# ESP32UsbHost.net
KiCad netlist of a schematic drawn in EAGLE
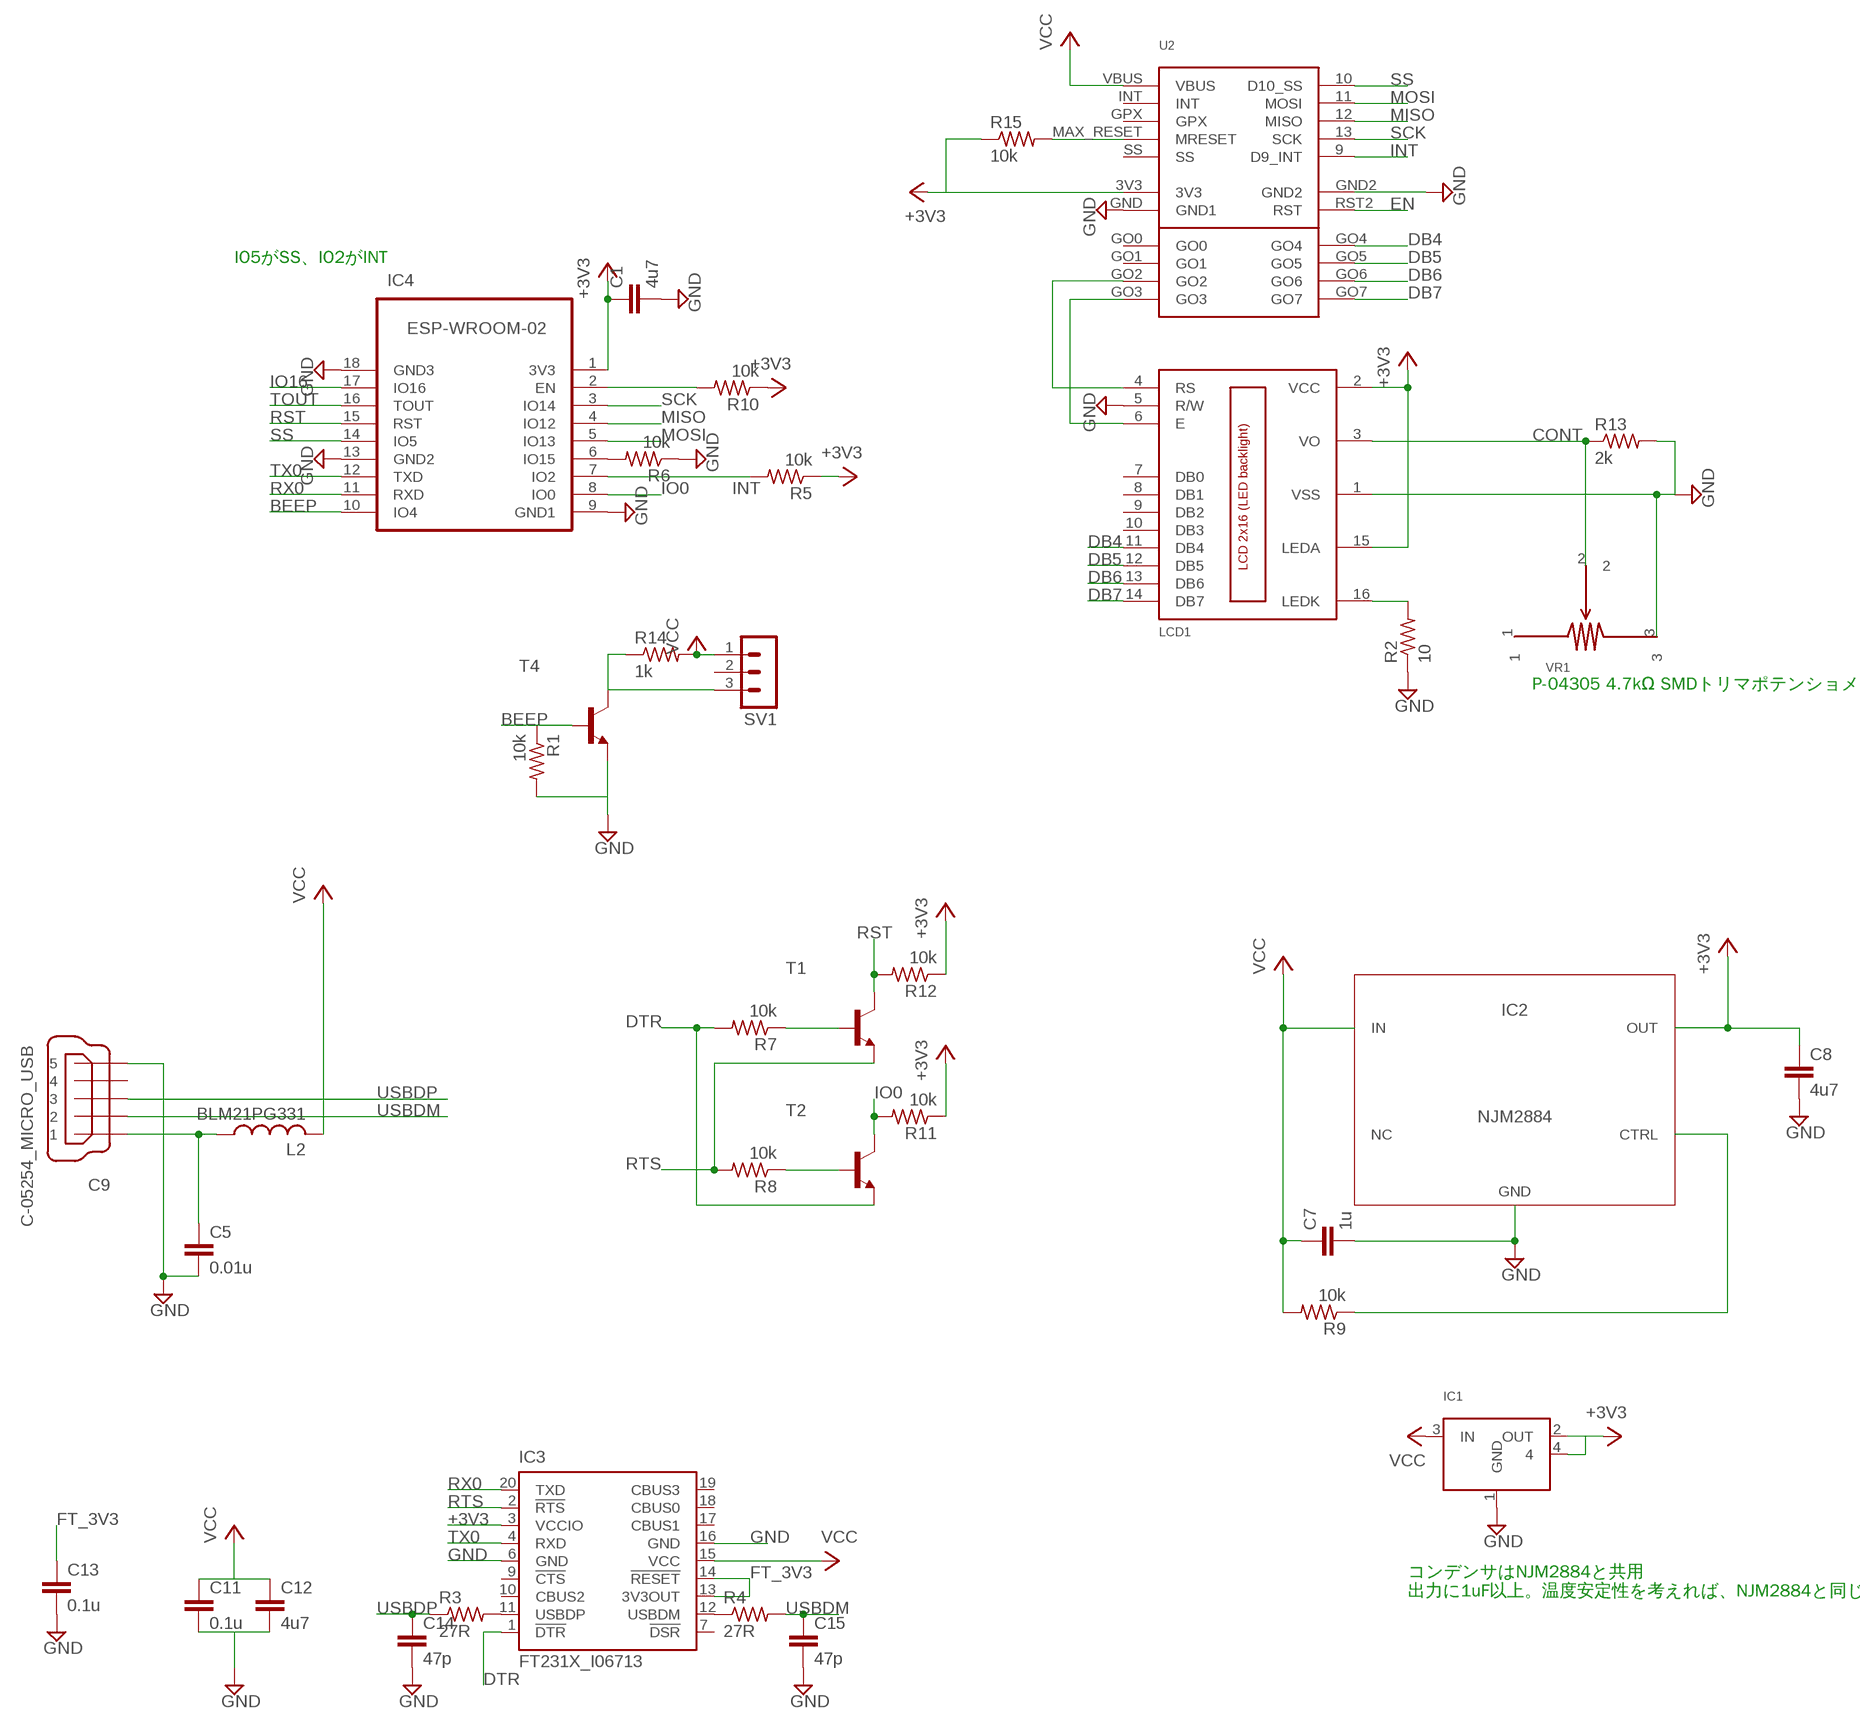
[diagram p0: schematic, sheet 1]

(export (version "E")
  (design (tool "Eeschema 10.0.6"))
  (components
    (comp (ref "C1")
      (value "4u7")
      (footprint "eagle-import:C0603")
      (libsource (lib "eagle-import") (part "C-EUC0603"))
    )
    (comp (ref "C5")
      (value "0.01u")
      (footprint "eagle-import:C0603")
      (libsource (lib "eagle-import") (part "C-EUC0603"))
    )
    (comp (ref "C7")
      (value "1u")
      (footprint "eagle-import:C0603")
      (libsource (lib "eagle-import") (part "C-EUC0603"))
    )
    (comp (ref "C8")
      (value "4u7")
      (footprint "eagle-import:C0603")
      (libsource (lib "eagle-import") (part "C-EUC0603"))
    )
    (comp (ref "C9")
      (value "C-05254_MICRO_USB")
      (footprint "eagle-import:C-05254_MICRO_USB")
      (libsource (lib "eagle-import") (part "C-05254_MICRO_USB"))
    )
    (comp (ref "C11")
      (value "0.1u")
      (footprint "eagle-import:C0603")
      (libsource (lib "eagle-import") (part "C-EUC0603"))
    )
    (comp (ref "C12")
      (value "4u7")
      (footprint "eagle-import:C0603")
      (libsource (lib "eagle-import") (part "C-EUC0603"))
    )
    (comp (ref "C13")
      (value "0.1u")
      (footprint "eagle-import:C0603")
      (libsource (lib "eagle-import") (part "C-EUC0603"))
    )
    (comp (ref "C14")
      (value "47p")
      (footprint "eagle-import:C0603")
      (libsource (lib "eagle-import") (part "C-EUC0603"))
    )
    (comp (ref "C15")
      (value "47p")
      (footprint "eagle-import:C0603")
      (libsource (lib "eagle-import") (part "C-EUC0603"))
    )
    (comp (ref "IC1")
      (value "I-12635_ADP3338AKCZ")
      (footprint "eagle-import:SOT223")
      (libsource (lib "eagle-import") (part "I-12635_ADP3338AKCZ"))
    )
    (comp (ref "IC2")
      (value "NJM2884")
      (footprint "eagle-import:SOT89-5")
      (libsource (lib "eagle-import") (part "NJM2884"))
    )
    (comp (ref "IC3")
      (value "FT231X_I06713")
      (footprint "eagle-import:SSOP20(2)")
      (libsource (lib "eagle-import") (part "FT231X_I06713"))
    )
    (comp (ref "IC4")
      (value "ESP-WROOM-02")
      (footprint "eagle-import:FRONT-FACE_HANDSOLDER")
      (libsource (lib "eagle-import") (part "ESP-WROOM-02"))
    )
    (comp (ref "L2")
      (value "BLM21PG331")
      (footprint "eagle-import:L2012C")
      (libsource (lib "eagle-import") (part "L-USL2012C"))
    )
    (comp (ref "LCD1")
      (value "LCD_2X16CONN_ONLY")
      (footprint "eagle-import:HY-1602F_2")
      (libsource (lib "eagle-import") (part "LCD_2X16CONN_ONLY"))
    )
    (comp (ref "R1")
      (value "10k")
      (footprint "eagle-import:R0603")
      (libsource (lib "eagle-import") (part "R-US_R0603"))
    )
    (comp (ref "R2")
      (value "10")
      (footprint "eagle-import:R0603")
      (libsource (lib "eagle-import") (part "R-US_R0603"))
    )
    (comp (ref "R3")
      (value "27R")
      (footprint "eagle-import:R0603")
      (libsource (lib "eagle-import") (part "R-US_R0603"))
    )
    (comp (ref "R4")
      (value "27R")
      (footprint "eagle-import:R0603")
      (libsource (lib "eagle-import") (part "R-US_R0603"))
    )
    (comp (ref "R5")
      (value "10k")
      (footprint "eagle-import:R0603")
      (libsource (lib "eagle-import") (part "R-US_R0603"))
    )
    (comp (ref "R6")
      (value "10k")
      (footprint "eagle-import:R0603")
      (libsource (lib "eagle-import") (part "R-US_R0603"))
    )
    (comp (ref "R7")
      (value "10k")
      (footprint "eagle-import:R0603")
      (libsource (lib "eagle-import") (part "R-US_R0603"))
    )
    (comp (ref "R8")
      (value "10k")
      (footprint "eagle-import:R0603")
      (libsource (lib "eagle-import") (part "R-US_R0603"))
    )
    (comp (ref "R9")
      (value "10k")
      (footprint "eagle-import:R0603")
      (libsource (lib "eagle-import") (part "R-US_R0603"))
    )
    (comp (ref "R10")
      (value "10k")
      (footprint "eagle-import:R0603")
      (libsource (lib "eagle-import") (part "R-US_R0603"))
    )
    (comp (ref "R11")
      (value "10k")
      (footprint "eagle-import:R0603")
      (libsource (lib "eagle-import") (part "R-US_R0603"))
    )
    (comp (ref "R12")
      (value "10k")
      (footprint "eagle-import:R0603")
      (libsource (lib "eagle-import") (part "R-US_R0603"))
    )
    (comp (ref "R13")
      (value "2k")
      (footprint "eagle-import:R0603")
      (libsource (lib "eagle-import") (part "R-US_R0603"))
    )
    (comp (ref "R14")
      (value "1k")
      (footprint "eagle-import:R0603")
      (libsource (lib "eagle-import") (part "R-US_R0603"))
    )
    (comp (ref "R15")
      (value "10k")
      (footprint "eagle-import:R0603")
      (libsource (lib "eagle-import") (part "R-US_R0603"))
    )
    (comp (ref "SV1")
      (value "MA03-1")
      (footprint "eagle-import:MA03-1")
      (libsource (lib "eagle-import") (part "MA03-1"))
    )
    (comp (ref "T1")
      (value "BC808-NPN-SOT23-BEC")
      (footprint "eagle-import:SOT23-BEC")
      (libsource (lib "eagle-import") (part "-NPN-SOT23-BECBC808"))
    )
    (comp (ref "T2")
      (value "BC808-NPN-SOT23-BEC")
      (footprint "eagle-import:SOT23-BEC")
      (libsource (lib "eagle-import") (part "-NPN-SOT23-BECBC808"))
    )
    (comp (ref "T4")
      (value "BC808-NPN-SOT23-BEC")
      (footprint "eagle-import:SOT23-BEC")
      (libsource (lib "eagle-import") (part "-NPN-SOT23-BECBC808"))
    )
    (comp (ref "U2")
      (value "USB_HOST_MINI")
      (footprint "eagle-import:USB_HOST_MINI")
      (libsource (lib "eagle-import") (part "USB_HOST_MINI"))
    )
    (comp (ref "VR1")
      (value "P-04305_PVZ3_VR_POTENTION_METER")
      (footprint "eagle-import:VR_POTENTION_METER")
      (libsource (lib "eagle-import") (part "P-04305_PVZ3_VR_POTENTION_METER"))
    )
  )
  (nets
    (net (code "1") (name "+3V3") (class "Default")
      (node (ref "C1") (pin "1") (pinfunction "1_1") (pintype "passive"))
      (node (ref "C8") (pin "1") (pinfunction "1_1") (pintype "passive"))
      (node (ref "IC1") (pin "2") (pinfunction "OUT_2") (pintype "bidirectional"))
      (node (ref "IC1") (pin "4") (pinfunction "4_4") (pintype "bidirectional"))
      (node (ref "IC2") (pin "4") (pinfunction "OUT_4") (pintype "passive"))
      (node (ref "IC3") (pin "3") (pinfunction "VCCIO_3") (pintype "power_in"))
      (node (ref "IC4") (pin "1") (pinfunction "3V3_1") (pintype "power_in"))
      (node (ref "LCD1") (pin "15") (pinfunction "LEDA_15") (pintype "passive"))
      (node (ref "LCD1") (pin "2") (pinfunction "VCC_2") (pintype "power_in"))
      (node (ref "R10") (pin "1") (pinfunction "1_1") (pintype "passive"))
      (node (ref "R11") (pin "1") (pinfunction "1_1") (pintype "passive"))
      (node (ref "R12") (pin "1") (pinfunction "1_1") (pintype "passive"))
      (node (ref "R15") (pin "1") (pinfunction "1_1") (pintype "passive"))
      (node (ref "R5") (pin "1") (pinfunction "1_1") (pintype "passive"))
      (node (ref "U2") (pin "3V3") (pinfunction "3V3_3V3") (pintype "bidirectional"))
    )
    (net (code "2") (name "/BEEP") (class "Default")
      (node (ref "IC4") (pin "10") (pinfunction "IO4_10") (pintype "bidirectional"))
      (node (ref "R1") (pin "1") (pinfunction "1_1") (pintype "passive"))
      (node (ref "T4") (pin "B") (pinfunction "B_B") (pintype "passive"))
    )
    (net (code "3") (name "/CONT") (class "Default")
      (node (ref "LCD1") (pin "3") (pinfunction "VO_3") (pintype "input"))
      (node (ref "R13") (pin "1") (pinfunction "1_1") (pintype "passive"))
      (node (ref "VR1") (pin "2") (pinfunction "2_2") (pintype "bidirectional"))
    )
    (net (code "4") (name "/DB4") (class "Default")
      (node (ref "LCD1") (pin "11") (pinfunction "DB4_11") (pintype "bidirectional"))
      (node (ref "U2") (pin "GO4") (pinfunction "GO4_GO4") (pintype "bidirectional"))
    )
    (net (code "5") (name "/DB5") (class "Default")
      (node (ref "LCD1") (pin "12") (pinfunction "DB5_12") (pintype "bidirectional"))
      (node (ref "U2") (pin "GO5") (pinfunction "GO5_GO5") (pintype "bidirectional"))
    )
    (net (code "6") (name "/DB6") (class "Default")
      (node (ref "LCD1") (pin "13") (pinfunction "DB6_13") (pintype "bidirectional"))
      (node (ref "U2") (pin "GO6") (pinfunction "GO6_GO6") (pintype "bidirectional"))
    )
    (net (code "7") (name "/DB7") (class "Default")
      (node (ref "LCD1") (pin "14") (pinfunction "DB7_14") (pintype "bidirectional"))
      (node (ref "U2") (pin "GO7") (pinfunction "GO7_GO7") (pintype "bidirectional"))
    )
    (net (code "8") (name "/DTR") (class "Default")
      (node (ref "IC3") (pin "1") (pinfunction "~{DTR}_1") (pintype "input"))
      (node (ref "R7") (pin "2") (pinfunction "2_2") (pintype "passive"))
      (node (ref "T2") (pin "E") (pinfunction "E_E") (pintype "passive"))
    )
    (net (code "9") (name "/EN") (class "Default")
      (node (ref "U2") (pin "RST2") (pinfunction "RST_RST2") (pintype "bidirectional"))
    )
    (net (code "10") (name "/FT_3V3") (class "Default")
      (node (ref "C13") (pin "1") (pinfunction "1_1") (pintype "passive"))
      (node (ref "IC3") (pin "13") (pinfunction "3V3OUT_13") (pintype "output"))
      (node (ref "IC3") (pin "14") (pinfunction "~{RESET}_14") (pintype "input"))
    )
    (net (code "11") (name "/INT") (class "Default")
      (node (ref "IC4") (pin "7") (pinfunction "IO2_7") (pintype "bidirectional"))
      (node (ref "R5") (pin "2") (pinfunction "2_2") (pintype "passive"))
      (node (ref "U2") (pin "9") (pinfunction "D9_INT_9") (pintype "bidirectional"))
    )
    (net (code "12") (name "/IO0") (class "Default")
      (node (ref "IC4") (pin "8") (pinfunction "IO0_8") (pintype "bidirectional"))
      (node (ref "R11") (pin "2") (pinfunction "2_2") (pintype "passive"))
      (node (ref "T2") (pin "C") (pinfunction "C_C") (pintype "passive"))
    )
    (net (code "13") (name "/IO16") (class "Default")
      (node (ref "IC4") (pin "17") (pinfunction "IO16_17") (pintype "bidirectional"))
    )
    (net (code "14") (name "/MISO") (class "Default")
      (node (ref "IC4") (pin "4") (pinfunction "IO12_4") (pintype "bidirectional"))
      (node (ref "U2") (pin "12") (pinfunction "MISO_12") (pintype "bidirectional"))
    )
    (net (code "15") (name "/MOSI") (class "Default")
      (node (ref "IC4") (pin "5") (pinfunction "IO13_5") (pintype "bidirectional"))
      (node (ref "U2") (pin "11") (pinfunction "MOSI_11") (pintype "bidirectional"))
    )
    (net (code "16") (name "/RST") (class "Default")
      (node (ref "IC4") (pin "15") (pinfunction "RST_15") (pintype "bidirectional"))
      (node (ref "R12") (pin "2") (pinfunction "2_2") (pintype "passive"))
      (node (ref "T1") (pin "C") (pinfunction "C_C") (pintype "passive"))
    )
    (net (code "17") (name "/RTS") (class "Default")
      (node (ref "IC3") (pin "2") (pinfunction "~{RTS}_2") (pintype "output"))
      (node (ref "R8") (pin "2") (pinfunction "2_2") (pintype "passive"))
      (node (ref "T1") (pin "E") (pinfunction "E_E") (pintype "passive"))
    )
    (net (code "18") (name "/RX0") (class "Default")
      (node (ref "IC3") (pin "20") (pinfunction "TXD_20") (pintype "output"))
      (node (ref "IC4") (pin "11") (pinfunction "RXD_11") (pintype "bidirectional"))
    )
    (net (code "19") (name "/SCK") (class "Default")
      (node (ref "IC4") (pin "3") (pinfunction "IO14_3") (pintype "bidirectional"))
      (node (ref "U2") (pin "13") (pinfunction "SCK_13") (pintype "bidirectional"))
    )
    (net (code "20") (name "/SS") (class "Default")
      (node (ref "IC4") (pin "14") (pinfunction "IO5_14") (pintype "open_collector"))
      (node (ref "U2") (pin "10") (pinfunction "D10_SS_10") (pintype "bidirectional"))
    )
    (net (code "21") (name "/TOUT") (class "Default")
      (node (ref "IC4") (pin "16") (pinfunction "TOUT_16") (pintype "bidirectional"))
    )
    (net (code "22") (name "/TX0") (class "Default")
      (node (ref "IC3") (pin "4") (pinfunction "RXD_4") (pintype "input"))
      (node (ref "IC4") (pin "12") (pinfunction "TXD_12") (pintype "bidirectional"))
    )
    (net (code "23") (name "/USBDM") (class "Default")
      (node (ref "C15") (pin "1") (pinfunction "1_1") (pintype "passive"))
      (node (ref "C9") (pin "2") (pinfunction "2_2") (pintype "passive"))
      (node (ref "R4") (pin "2") (pinfunction "2_2") (pintype "passive"))
    )
    (net (code "24") (name "/USBDP") (class "Default")
      (node (ref "C14") (pin "1") (pinfunction "1_1") (pintype "passive"))
      (node (ref "C9") (pin "3") (pinfunction "3_3") (pintype "passive"))
      (node (ref "R3") (pin "1") (pinfunction "1_1") (pintype "passive"))
    )
    (net (code "25") (name "GND") (class "Default")
      (node (ref "C1") (pin "2") (pinfunction "2_2") (pintype "passive"))
      (node (ref "C11") (pin "2") (pinfunction "2_2") (pintype "passive"))
      (node (ref "C12") (pin "2") (pinfunction "2_2") (pintype "passive"))
      (node (ref "C13") (pin "2") (pinfunction "2_2") (pintype "passive"))
      (node (ref "C14") (pin "2") (pinfunction "2_2") (pintype "passive"))
      (node (ref "C15") (pin "2") (pinfunction "2_2") (pintype "passive"))
      (node (ref "C5") (pin "2") (pinfunction "2_2") (pintype "passive"))
      (node (ref "C7") (pin "2") (pinfunction "2_2") (pintype "passive"))
      (node (ref "C8") (pin "2") (pinfunction "2_2") (pintype "passive"))
      (node (ref "C9") (pin "5") (pinfunction "5_5") (pintype "passive"))
      (node (ref "IC1") (pin "1") (pinfunction "GND_1") (pintype "bidirectional"))
      (node (ref "IC2") (pin "2") (pinfunction "GND_2") (pintype "passive"))
      (node (ref "IC3") (pin "16") (pinfunction "GND_16") (pintype "power_in"))
      (node (ref "IC3") (pin "6") (pinfunction "GND_6") (pintype "power_in"))
      (node (ref "IC4") (pin "13") (pinfunction "GND2_13") (pintype "power_in"))
      (node (ref "IC4") (pin "18") (pinfunction "GND3_18") (pintype "power_in"))
      (node (ref "IC4") (pin "9") (pinfunction "GND1_9") (pintype "power_in"))
      (node (ref "LCD1") (pin "1") (pinfunction "VSS_1") (pintype "power_in"))
      (node (ref "LCD1") (pin "5") (pinfunction "R/W_5") (pintype "input"))
      (node (ref "R1") (pin "2") (pinfunction "2_2") (pintype "passive"))
      (node (ref "R13") (pin "2") (pinfunction "2_2") (pintype "passive"))
      (node (ref "R2") (pin "1") (pinfunction "1_1") (pintype "passive"))
      (node (ref "R6") (pin "1") (pinfunction "1_1") (pintype "passive"))
      (node (ref "T4") (pin "E") (pinfunction "E_E") (pintype "passive"))
      (node (ref "U2") (pin "GND") (pinfunction "GND1_GND") (pintype "bidirectional"))
      (node (ref "U2") (pin "GND2") (pinfunction "GND2_GND2") (pintype "bidirectional"))
      (node (ref "VR1") (pin "3") (pinfunction "3_3") (pintype "bidirectional"))
    )
    (net (code "26") (name "Net-(C5-Pad1)") (class "Default")
      (node (ref "C5") (pin "1") (pinfunction "1_1") (pintype "passive"))
      (node (ref "C9") (pin "1") (pinfunction "1_1") (pintype "passive"))
      (node (ref "L2") (pin "1") (pinfunction "1_1") (pintype "passive"))
    )
    (net (code "27") (name "Net-(IC2-CTRL)") (class "Default")
      (node (ref "IC2") (pin "1") (pinfunction "CTRL_1") (pintype "passive"))
      (node (ref "R9") (pin "1") (pinfunction "1_1") (pintype "passive"))
    )
    (net (code "28") (name "Net-(IC3-USBDM)") (class "Default")
      (node (ref "IC3") (pin "12") (pinfunction "USBDM_12") (pintype "input"))
      (node (ref "R4") (pin "1") (pinfunction "1_1") (pintype "passive"))
    )
    (net (code "29") (name "Net-(IC3-USBDP)") (class "Default")
      (node (ref "IC3") (pin "11") (pinfunction "USBDP_11") (pintype "input"))
      (node (ref "R3") (pin "2") (pinfunction "2_2") (pintype "passive"))
    )
    (net (code "30") (name "Net-(IC4-EN)") (class "Default")
      (node (ref "IC4") (pin "2") (pinfunction "EN_2") (pintype "bidirectional"))
      (node (ref "R10") (pin "2") (pinfunction "2_2") (pintype "passive"))
    )
    (net (code "31") (name "Net-(IC4-IO15)") (class "Default")
      (node (ref "IC4") (pin "6") (pinfunction "IO15_6") (pintype "bidirectional"))
      (node (ref "R6") (pin "2") (pinfunction "2_2") (pintype "passive"))
    )
    (net (code "32") (name "Net-(LCD1-E)") (class "Default")
      (node (ref "LCD1") (pin "6") (pinfunction "E_6") (pintype "input"))
      (node (ref "U2") (pin "GO3") (pinfunction "GO3_GO3") (pintype "bidirectional"))
    )
    (net (code "33") (name "Net-(LCD1-LEDK)") (class "Default")
      (node (ref "LCD1") (pin "16") (pinfunction "LEDK_16") (pintype "passive"))
      (node (ref "R2") (pin "2") (pinfunction "2_2") (pintype "passive"))
    )
    (net (code "34") (name "Net-(LCD1-RS)") (class "Default")
      (node (ref "LCD1") (pin "4") (pinfunction "RS_4") (pintype "input"))
      (node (ref "U2") (pin "GO2") (pinfunction "GO2_GO2") (pintype "bidirectional"))
    )
    (net (code "35") (name "Net-(R7-Pad1)") (class "Default")
      (node (ref "R7") (pin "1") (pinfunction "1_1") (pintype "passive"))
      (node (ref "T1") (pin "B") (pinfunction "B_B") (pintype "passive"))
    )
    (net (code "36") (name "Net-(R8-Pad1)") (class "Default")
      (node (ref "R8") (pin "1") (pinfunction "1_1") (pintype "passive"))
      (node (ref "T2") (pin "B") (pinfunction "B_B") (pintype "passive"))
    )
    (net (code "37") (name "Net-(R14-Pad1)") (class "Default")
      (node (ref "R14") (pin "1") (pinfunction "1_1") (pintype "passive"))
      (node (ref "SV1") (pin "3") (pinfunction "3_3") (pintype "passive"))
      (node (ref "T4") (pin "C") (pinfunction "C_C") (pintype "passive"))
    )
    (net (code "38") (name "Net-(U2-MRESET)") (class "Default")
      (node (ref "R15") (pin "2") (pinfunction "2_2") (pintype "passive"))
      (node (ref "U2") (pin "MAX_RESET") (pinfunction "MRESET_MAX_RESET") (pintype "bidirectional"))
    )
    (net (code "39") (name "VCC") (class "Default")
      (node (ref "C11") (pin "1") (pinfunction "1_1") (pintype "passive"))
      (node (ref "C12") (pin "1") (pinfunction "1_1") (pintype "passive"))
      (node (ref "C7") (pin "1") (pinfunction "1_1") (pintype "passive"))
      (node (ref "IC1") (pin "3") (pinfunction "IN_3") (pintype "bidirectional"))
      (node (ref "IC2") (pin "5") (pinfunction "IN_5") (pintype "passive"))
      (node (ref "IC3") (pin "15") (pinfunction "VCC_15") (pintype "power_in"))
      (node (ref "L2") (pin "2") (pinfunction "2_2") (pintype "passive"))
      (node (ref "R14") (pin "2") (pinfunction "2_2") (pintype "passive"))
      (node (ref "R9") (pin "2") (pinfunction "2_2") (pintype "passive"))
      (node (ref "SV1") (pin "1") (pinfunction "1_1") (pintype "passive"))
      (node (ref "U2") (pin "VBUS") (pinfunction "VBUS_VBUS") (pintype "bidirectional"))
    )
    (net (code "40") (name "unconnected-(C9-Pad4)") (class "Default")
      (node (ref "C9") (pin "4") (pinfunction "4_4") (pintype "passive"))
    )
    (net (code "41") (name "unconnected-(IC2-NC-Pad3)") (class "Default")
      (node (ref "IC2") (pin "3") (pinfunction "NC_3") (pintype "passive"))
    )
    (net (code "42") (name "unconnected-(IC3-CBUS0-Pad18)") (class "Default")
      (node (ref "IC3") (pin "18") (pinfunction "CBUS0_18") (pintype "bidirectional"))
    )
    (net (code "43") (name "unconnected-(IC3-CBUS1-Pad17)") (class "Default")
      (node (ref "IC3") (pin "17") (pinfunction "CBUS1_17") (pintype "bidirectional"))
    )
    (net (code "44") (name "unconnected-(IC3-CBUS2-Pad10)") (class "Default")
      (node (ref "IC3") (pin "10") (pinfunction "CBUS2_10") (pintype "bidirectional"))
    )
    (net (code "45") (name "unconnected-(IC3-CBUS3-Pad19)") (class "Default")
      (node (ref "IC3") (pin "19") (pinfunction "CBUS3_19") (pintype "bidirectional"))
    )
    (net (code "46") (name "unconnected-(IC3-~{CTS}-Pad9)") (class "Default")
      (node (ref "IC3") (pin "9") (pinfunction "~{CTS}_9") (pintype "input"))
    )
    (net (code "47") (name "unconnected-(IC3-~{DSR}-Pad7)") (class "Default")
      (node (ref "IC3") (pin "7") (pinfunction "~{DSR}_7") (pintype "input"))
    )
    (net (code "48") (name "unconnected-(LCD1-DB0-Pad7)") (class "Default")
      (node (ref "LCD1") (pin "7") (pinfunction "DB0_7") (pintype "bidirectional"))
    )
    (net (code "49") (name "unconnected-(LCD1-DB1-Pad8)") (class "Default")
      (node (ref "LCD1") (pin "8") (pinfunction "DB1_8") (pintype "bidirectional"))
    )
    (net (code "50") (name "unconnected-(LCD1-DB2-Pad9)") (class "Default")
      (node (ref "LCD1") (pin "9") (pinfunction "DB2_9") (pintype "bidirectional"))
    )
    (net (code "51") (name "unconnected-(LCD1-DB3-Pad10)") (class "Default")
      (node (ref "LCD1") (pin "10") (pinfunction "DB3_10") (pintype "bidirectional"))
    )
    (net (code "52") (name "unconnected-(SV1-Pad2)") (class "Default")
      (node (ref "SV1") (pin "2") (pinfunction "2_2") (pintype "passive"))
    )
    (net (code "53") (name "unconnected-(U2-PadGO0)") (class "Default")
      (node (ref "U2") (pin "GO0") (pinfunction "GO0_GO0") (pintype "bidirectional"))
    )
    (net (code "54") (name "unconnected-(U2-PadGO1)") (class "Default")
      (node (ref "U2") (pin "GO1") (pinfunction "GO1_GO1") (pintype "bidirectional"))
    )
    (net (code "55") (name "unconnected-(U2-PadGPX)") (class "Default")
      (node (ref "U2") (pin "GPX") (pinfunction "GPX_GPX") (pintype "bidirectional"))
    )
    (net (code "56") (name "unconnected-(U2-PadINT)") (class "Default")
      (node (ref "U2") (pin "INT") (pinfunction "INT_INT") (pintype "bidirectional"))
    )
    (net (code "57") (name "unconnected-(U2-PadSS)") (class "Default")
      (node (ref "U2") (pin "SS") (pinfunction "SS_SS") (pintype "bidirectional"))
    )
    (net (code "58") (name "unconnected-(VR1-Pad1)") (class "Default")
      (node (ref "VR1") (pin "1") (pinfunction "1_1") (pintype "bidirectional"))
    )
  )
)
